# 2_Power_Supply.net
KiCad netlist of a schematic drawn in Altium Designer
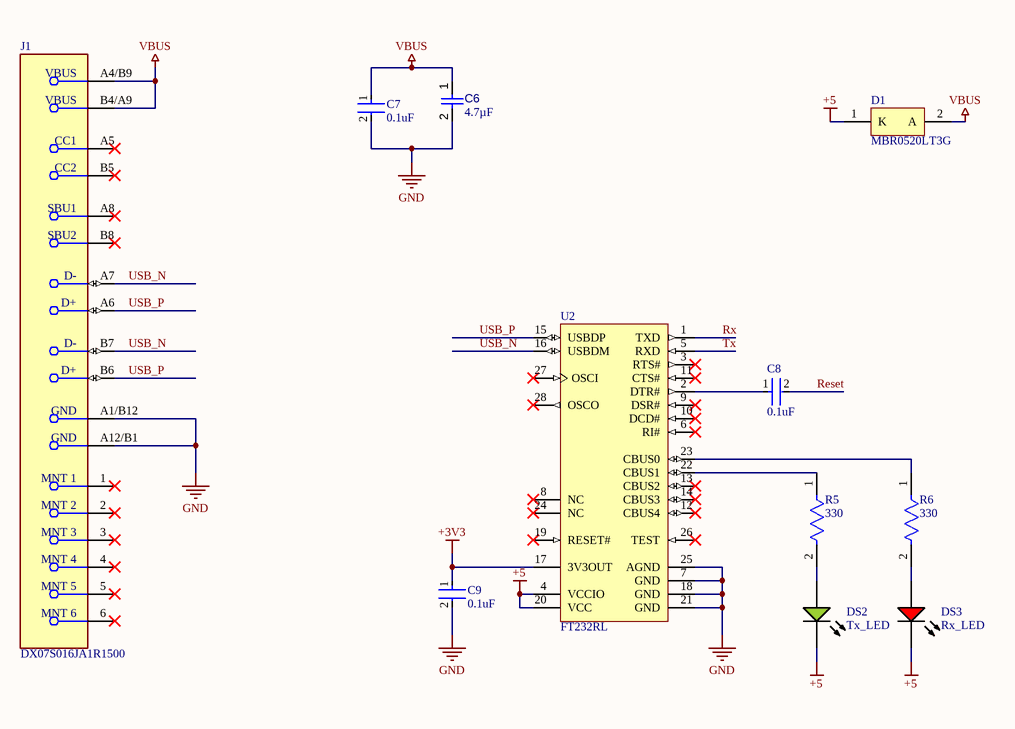
[diagram p0: 2_Power_Supply.SchDoc]

(export (version "E")
  (design (tool "Eeschema 10.0.6"))
  (components
    (comp (ref "C6")
      (value "4.7µF")
      (footprint "CAPC0805(2012)145_L")
      (description "Chip Capacitor, 4.7µF +/-40%, 25V, 0805, Thickness 1.45 mm")
      (fields (field (name "TOLERANCE") "20%") (field (name "Comment") "Capacitor 4.7µF +/-40% 25V 0805"))
      (libsource (lib "Hochschule Ravensburg Weingarten") (part "CAP-NP-2"))
    )
    (comp (ref "C7")
      (value "0.1uF")
      (footprint "FP-C0805C-DN-MFG")
      (description "C0805 0.10 μF X7R 30ppm/°C 20.00% 50 V")
      (fields
        (field (name "MANUFACTURER PART NUMBER") "C0805C104M5RAC")
        (field (name "MANUFACTURER") "KEMET")
      )
      (libsource (lib "Altium Content Vault") (part "b4654b650e69147ec39a6b967a45e02"))
    )
    (comp (ref "C8")
      (value "0.1uF")
      (footprint "FP-C0805C-DN-MFG")
      (description "C0805 0.10 μF X7R 30ppm/°C 20.00% 50 V")
      (fields
        (field (name "MANUFACTURER PART NUMBER") "C0805C104M5RAC")
        (field (name "MANUFACTURER") "KEMET")
      )
      (libsource (lib "Altium Content Vault") (part "b4654b650e69147ec39a6b967a45e02"))
    )
    (comp (ref "C9")
      (value "0.1uF")
      (footprint "FP-C0805C-DN-MFG")
      (description "C0805 0.10 μF X7R 30ppm/°C 20.00% 50 V")
      (fields
        (field (name "MANUFACTURER PART NUMBER") "C0805C104M5RAC")
        (field (name "MANUFACTURER") "KEMET")
      )
      (libsource (lib "Altium Content Vault") (part "b4654b650e69147ec39a6b967a45e02"))
    )
    (comp (ref "D1")
      (value "MBR0520LT3G")
      (footprint "ONSC-SOD-123-2-425-04_V")
      (description "Schottky Power Rectifier, 2-Pin SOD-123, Pb-Free, Tape and Reel")
      (fields (field (name "MANUFACTURER") "On Semiconductor"))
      (libsource (lib "Altium Content Vault") (part "ONSC-D-K1A2-2_A"))
    )
    (comp (ref "DS2")
      (value "Tx_LED")
      (footprint "EVRL-0603-2_V")
      (description "Chip LED, Yellow-Green, 5 V, 25 mA, -40 to 85 degC, 2-Pin SMD (0603), RoHS, Tape and Reel")
      (fields (field (name "MANUFACTURER") "Everlight Electronics"))
      (libsource (lib "Hochschule Ravensburg Weingarten") (part "LED-YELLOW-GREEN-AK-2"))
    )
    (comp (ref "DS3")
      (value "Rx_LED")
      (footprint "EVRL-0603-2_V")
      (description "Chip LED, Red, 5 V, 25 mA, -40 to 85 degC, 2-Pin SMD (0603), RoHS, Tape and Reel")
      (fields (field (name "MANUFACTURER") "Everlight Electronics"))
      (libsource (lib "Hochschule Ravensburg Weingarten") (part "LED-RED-AK-2"))
    )
    (comp (ref "J1")
      (value "DX07S016JA1R1500")
      (footprint "FP-DX07S016JA1R1500-MFG")
      (description "CONN RCP USB2.0 TYP C 24P SMD RA")
      (libsource (lib "Altium Content Vault") (part "7f3e9989102a0f22bff9cb010881d34"))
    )
    (comp (ref "R5")
      (value "330")
      (footprint "FP-CRCW0805-e3-MFG")
      (description "RES Thick Film, 330Ω, 1%, 0.125W, 100ppm/°C, 0805")
      (fields (field (name "TOLERANCE") "1%"))
      (libsource (lib "Altium Content Vault") (part "1029c3af85768c4190bb7ad29bc67b5"))
    )
    (comp (ref "R6")
      (value "330")
      (footprint "FP-CRCW0805-e3-MFG")
      (description "RES Thick Film, 330Ω, 1%, 0.125W, 100ppm/°C, 0805")
      (fields (field (name "TOLERANCE") "1%"))
      (libsource (lib "Altium Content Vault") (part "1029c3af85768c4190bb7ad29bc67b5"))
    )
    (comp (ref "U2")
      (value "FT232RL")
      (footprint "FTDI-SSOP-28_M")
      (description "IC USB FS SERIAL UART 28-SSOP")
      (fields (field (name "MANUFACTURER") "FTDI"))
      (libsource (lib "Altium Content Vault") (part "FTDI-FT232-SSOP-28"))
    )
  )
  (nets
    (net (code "1") (name "+3V3") (class "Default")
      (node (ref "C9") (pin "1") (pinfunction "1_1") (pintype "passive"))
      (node (ref "U2") (pin "17") (pinfunction "3V3OUT_17") (pintype "power_in"))
    )
    (net (code "2") (name "+5") (class "Default")
      (node (ref "D1") (pin "1") (pinfunction "K_1") (pintype "passive"))
      (node (ref "DS2") (pin "2") (pinfunction "K_2") (pintype "passive"))
      (node (ref "DS3") (pin "2") (pinfunction "K_2") (pintype "passive"))
      (node (ref "U2") (pin "20") (pinfunction "VCC_20") (pintype "power_in"))
      (node (ref "U2") (pin "4") (pinfunction "VCCIO_4") (pintype "power_in"))
    )
    (net (code "3") (name "/Reset") (class "Default")
      (node (ref "C8") (pin "2") (pinfunction "2_2") (pintype "passive"))
    )
    (net (code "4") (name "/Rx") (class "Default")
      (node (ref "U2") (pin "1") (pinfunction "TXD_1") (pintype "output"))
    )
    (net (code "5") (name "/Tx") (class "Default")
      (node (ref "U2") (pin "5") (pinfunction "RXD_5") (pintype "input"))
    )
    (net (code "6") (name "/USB_N") (class "Default")
      (node (ref "J1") (pin "A7") (pinfunction "D-_A7") (pintype "bidirectional"))
      (node (ref "J1") (pin "B7") (pinfunction "D-_B7") (pintype "bidirectional"))
      (node (ref "U2") (pin "16") (pinfunction "USBDM_16") (pintype "bidirectional"))
    )
    (net (code "7") (name "/USB_P") (class "Default")
      (node (ref "J1") (pin "A6") (pinfunction "D+_A6") (pintype "bidirectional"))
      (node (ref "J1") (pin "B6") (pinfunction "D+_B6") (pintype "bidirectional"))
      (node (ref "U2") (pin "15") (pinfunction "USBDP_15") (pintype "bidirectional"))
    )
    (net (code "8") (name "GND") (class "Default")
      (node (ref "C6") (pin "2") (pinfunction "2_2") (pintype "passive"))
      (node (ref "C7") (pin "2") (pinfunction "2_2") (pintype "passive"))
      (node (ref "C9") (pin "2") (pinfunction "2_2") (pintype "passive"))
      (node (ref "J1") (pin "A1/B12") (pinfunction "GND_A1/B12") (pintype "power_in"))
      (node (ref "J1") (pin "A12/B1") (pinfunction "GND_A12/B1") (pintype "power_in"))
      (node (ref "U2") (pin "18") (pinfunction "GND_18") (pintype "power_in"))
      (node (ref "U2") (pin "21") (pinfunction "GND_21") (pintype "power_in"))
      (node (ref "U2") (pin "25") (pinfunction "AGND_25") (pintype "power_in"))
      (node (ref "U2") (pin "7") (pinfunction "GND_7") (pintype "power_in"))
    )
    (net (code "9") (name "Net-(DS2-A)") (class "Default")
      (node (ref "DS2") (pin "1") (pinfunction "A_1") (pintype "passive"))
      (node (ref "R5") (pin "2") (pinfunction "2_2") (pintype "passive"))
    )
    (net (code "10") (name "Net-(DS3-A)") (class "Default")
      (node (ref "DS3") (pin "1") (pinfunction "A_1") (pintype "passive"))
      (node (ref "R6") (pin "2") (pinfunction "2_2") (pintype "passive"))
    )
    (net (code "11") (name "Net-(U2-CBUS0)") (class "Default")
      (node (ref "R6") (pin "1") (pinfunction "1_1") (pintype "passive"))
      (node (ref "U2") (pin "23") (pinfunction "CBUS0_23") (pintype "bidirectional"))
    )
    (net (code "12") (name "Net-(U2-CBUS1)") (class "Default")
      (node (ref "R5") (pin "1") (pinfunction "1_1") (pintype "passive"))
      (node (ref "U2") (pin "22") (pinfunction "CBUS1_22") (pintype "bidirectional"))
    )
    (net (code "13") (name "Net-(U2-DTR#)") (class "Default")
      (node (ref "C8") (pin "1") (pinfunction "1_1") (pintype "passive"))
      (node (ref "U2") (pin "2") (pinfunction "DTR#_2") (pintype "output"))
    )
    (net (code "14") (name "VBUS") (class "Default")
      (node (ref "C6") (pin "1") (pinfunction "1_1") (pintype "passive"))
      (node (ref "C7") (pin "1") (pinfunction "1_1") (pintype "passive"))
      (node (ref "D1") (pin "2") (pinfunction "A_2") (pintype "passive"))
      (node (ref "J1") (pin "A4/B9") (pinfunction "VBUS_A4/B9") (pintype "power_in"))
      (node (ref "J1") (pin "B4/A9") (pinfunction "VBUS_B4/A9") (pintype "power_in"))
    )
    (net (code "15") (name "unconnected-(J1-CC1-PadA5)") (class "Default")
      (node (ref "J1") (pin "A5") (pinfunction "CC1_A5") (pintype "passive+no_connect"))
    )
    (net (code "16") (name "unconnected-(J1-CC2-PadB5)") (class "Default")
      (node (ref "J1") (pin "B5") (pinfunction "CC2_B5") (pintype "passive+no_connect"))
    )
    (net (code "17") (name "unconnected-(J1-MNT_1-Pad1)") (class "Default")
      (node (ref "J1") (pin "1") (pinfunction "MNT_1_1") (pintype "passive+no_connect"))
    )
    (net (code "18") (name "unconnected-(J1-MNT_2-Pad2)") (class "Default")
      (node (ref "J1") (pin "2") (pinfunction "MNT_2_2") (pintype "passive+no_connect"))
    )
    (net (code "19") (name "unconnected-(J1-MNT_3-Pad3)") (class "Default")
      (node (ref "J1") (pin "3") (pinfunction "MNT_3_3") (pintype "passive+no_connect"))
    )
    (net (code "20") (name "unconnected-(J1-MNT_4-Pad4)") (class "Default")
      (node (ref "J1") (pin "4") (pinfunction "MNT_4_4") (pintype "passive+no_connect"))
    )
    (net (code "21") (name "unconnected-(J1-MNT_5-Pad5)") (class "Default")
      (node (ref "J1") (pin "5") (pinfunction "MNT_5_5") (pintype "passive+no_connect"))
    )
    (net (code "22") (name "unconnected-(J1-MNT_6-Pad6)") (class "Default")
      (node (ref "J1") (pin "6") (pinfunction "MNT_6_6") (pintype "passive+no_connect"))
    )
    (net (code "23") (name "unconnected-(J1-SBU1-PadA8)") (class "Default")
      (node (ref "J1") (pin "A8") (pinfunction "SBU1_A8") (pintype "passive+no_connect"))
    )
    (net (code "24") (name "unconnected-(J1-SBU2-PadB8)") (class "Default")
      (node (ref "J1") (pin "B8") (pinfunction "SBU2_B8") (pintype "passive+no_connect"))
    )
    (net (code "25") (name "unconnected-(U2-CBUS2-Pad13)") (class "Default")
      (node (ref "U2") (pin "13") (pinfunction "CBUS2_13") (pintype "bidirectional+no_connect"))
    )
    (net (code "26") (name "unconnected-(U2-CBUS3-Pad14)") (class "Default")
      (node (ref "U2") (pin "14") (pinfunction "CBUS3_14") (pintype "bidirectional+no_connect"))
    )
    (net (code "27") (name "unconnected-(U2-CBUS4-Pad12)") (class "Default")
      (node (ref "U2") (pin "12") (pinfunction "CBUS4_12") (pintype "bidirectional+no_connect"))
    )
    (net (code "28") (name "unconnected-(U2-CTS#-Pad11)") (class "Default")
      (node (ref "U2") (pin "11") (pinfunction "CTS#_11") (pintype "input+no_connect"))
    )
    (net (code "29") (name "unconnected-(U2-DCD#-Pad10)") (class "Default")
      (node (ref "U2") (pin "10") (pinfunction "DCD#_10") (pintype "input+no_connect"))
    )
    (net (code "30") (name "unconnected-(U2-DSR#-Pad9)") (class "Default")
      (node (ref "U2") (pin "9") (pinfunction "DSR#_9") (pintype "input+no_connect"))
    )
    (net (code "31") (name "unconnected-(U2-NC-Pad8)") (class "Default")
      (node (ref "U2") (pin "8") (pinfunction "NC_8") (pintype "passive+no_connect"))
    )
    (net (code "32") (name "unconnected-(U2-NC-Pad24)") (class "Default")
      (node (ref "U2") (pin "24") (pinfunction "NC_24") (pintype "passive+no_connect"))
    )
    (net (code "33") (name "unconnected-(U2-OSCI-Pad27)") (class "Default")
      (node (ref "U2") (pin "27") (pinfunction "OSCI_27") (pintype "input+no_connect"))
    )
    (net (code "34") (name "unconnected-(U2-OSCO-Pad28)") (class "Default")
      (node (ref "U2") (pin "28") (pinfunction "OSCO_28") (pintype "output+no_connect"))
    )
    (net (code "35") (name "unconnected-(U2-RESET#-Pad19)") (class "Default")
      (node (ref "U2") (pin "19") (pinfunction "RESET#_19") (pintype "input+no_connect"))
    )
    (net (code "36") (name "unconnected-(U2-RI#-Pad6)") (class "Default")
      (node (ref "U2") (pin "6") (pinfunction "RI#_6") (pintype "input+no_connect"))
    )
    (net (code "37") (name "unconnected-(U2-RTS#-Pad3)") (class "Default")
      (node (ref "U2") (pin "3") (pinfunction "RTS#_3") (pintype "output+no_connect"))
    )
    (net (code "38") (name "unconnected-(U2-TEST-Pad26)") (class "Default")
      (node (ref "U2") (pin "26") (pinfunction "TEST_26") (pintype "input+no_connect"))
    )
  )
)
